# PORT.net
KiCad netlist of a schematic drawn in Altium Designer
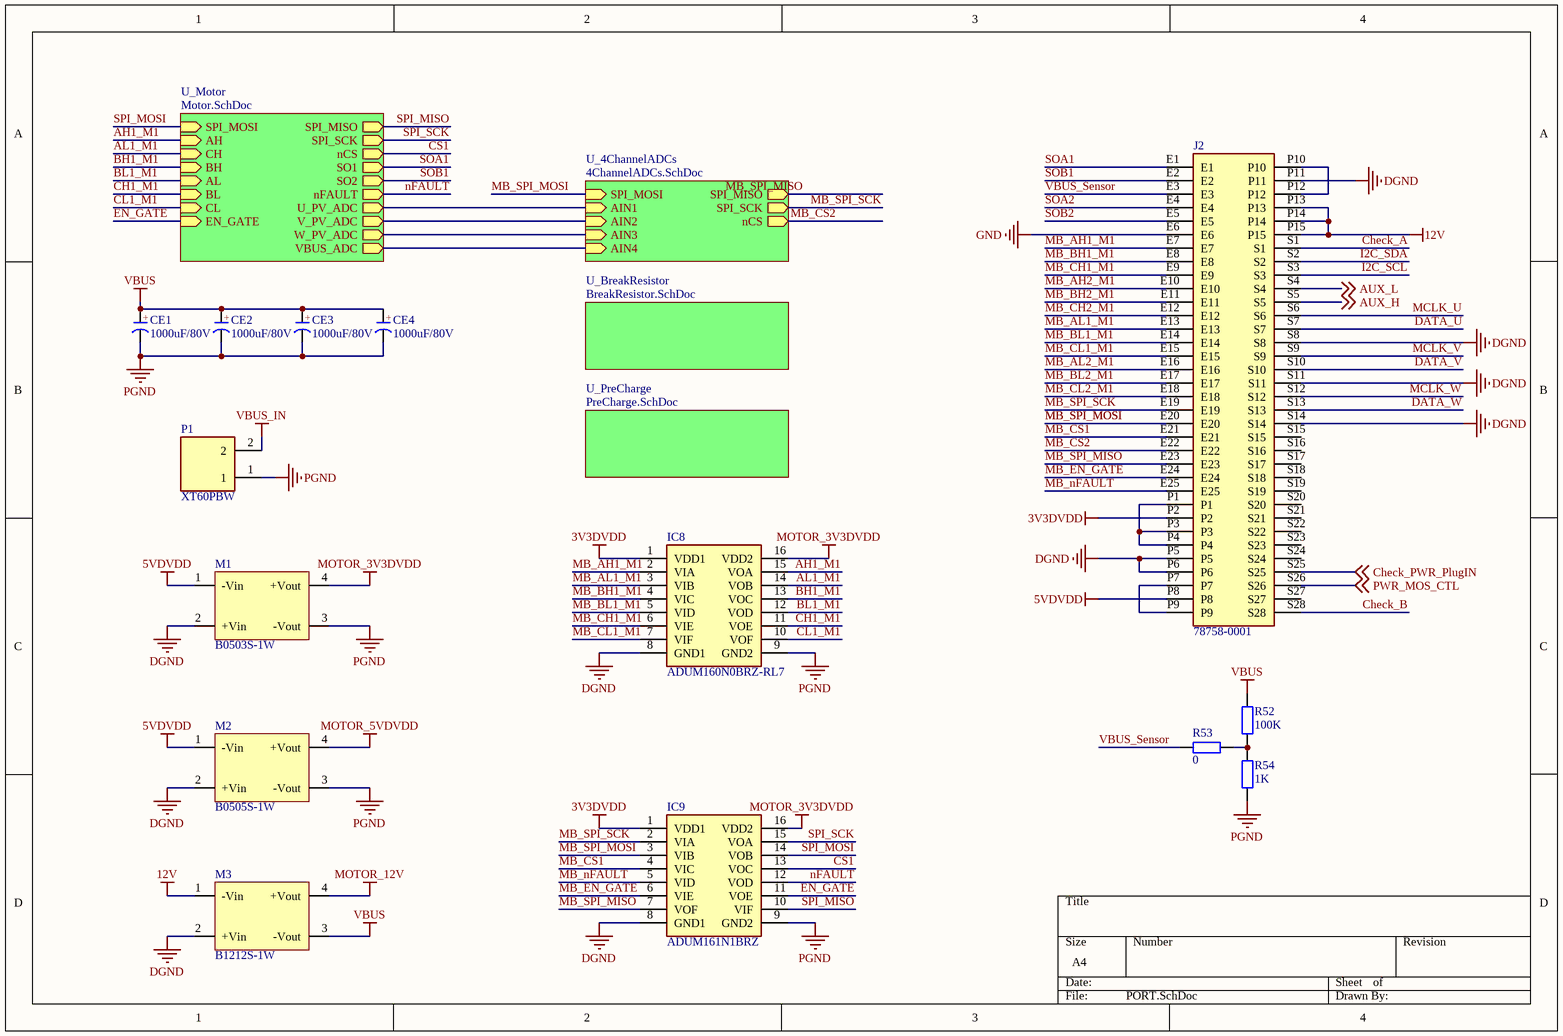
[diagram p0: PORT.SchDoc]

(export (version "E")
  (design (tool "Eeschema 10.0.6"))
  (components
    (comp (ref "CE1")
      (value "1000uF/80V")
      (footprint "CAP 7.5*18*35.5 - BK")
      (description "直插电解电容")
      (libsource (lib "0.1 - 电阻-电容-电感") (part "CE"))
    )
    (comp (ref "CE2")
      (value "1000uF/80V")
      (footprint "CAP 7.5*18*35.5 - BK")
      (description "直插电解电容")
      (libsource (lib "0.1 - 电阻-电容-电感") (part "CE"))
    )
    (comp (ref "CE3")
      (value "1000uF/80V")
      (footprint "CAP 7.5*18*35.5 - BK")
      (description "直插电解电容")
      (libsource (lib "0.1 - 电阻-电容-电感") (part "CE"))
    )
    (comp (ref "CE4")
      (value "1000uF/80V")
      (footprint "CAP 7.5*18*35.5 - BK")
      (description "直插电解电容")
      (libsource (lib "0.1 - 电阻-电容-电感") (part "CE"))
    )
    (comp (ref "IC8")
      (value "ADUM160N0BRZ-RL7")
      (footprint "SkylakeADPcbLib:SOIC127P600X175-16N")
      (description "Integrated Circuit")
      (fields (field (name "MOUSER PART NUMBER") "584-ADUM160N0BRZ-RL7"))
      (libsource (lib "*") (part "ADUM160N0BRZ-RL7"))
    )
    (comp (ref "IC9")
      (value "ADUM161N1BRZ")
      (footprint "SkylakeADPcbLib:SOIC127P600X175-16N")
      (description "Integrated Circuit")
      (fields (field (name "MOUSER PART NUMBER") "584-ADUM161N1BRZ"))
      (libsource (lib "*") (part "ADUM161N1BRZ"))
    )
    (comp (ref "J2")
      (value "78758-0001")
      (footprint "SkylakeADPcbLib:78758-0001")
      (description "Connector")
      (fields (field (name "MOUSER PART NUMBER") "538-78758-0001"))
      (libsource (lib "*") (part "78758-0001"))
    )
    (comp (ref "M1")
      (value "B0503S-1W")
      (footprint "B0505S-1W")
      (description "DC-DC模块")
      (fields (field (name "版权归属") "封装库来自淘宝 ID：黄晶宝石"))
      (libsource (lib "0.9 - 模块") (part "B0505S-1W"))
    )
    (comp (ref "M2")
      (value "B0505S-1W")
      (footprint "B0505S-1W")
      (description "DC-DC模块")
      (fields (field (name "版权归属") "封装库来自淘宝 ID：黄晶宝石"))
      (libsource (lib "0.9 - 模块") (part "B0505S-1W"))
    )
    (comp (ref "M3")
      (value "B1212S-1W")
      (footprint "B0505S-1W")
      (description "DC-DC模块")
      (fields (field (name "版权归属") "封装库来自淘宝 ID：黄晶宝石"))
      (libsource (lib "0.9 - 模块") (part "B0505S-1W"))
    )
    (comp (ref "P1")
      (value "XT60PBW")
      (footprint "XT60")
      (libsource (lib "SkylakeADSchLib") (part "XT60PBW"))
    )
    (comp (ref "R52")
      (value "100K")
      (footprint "R 0603_L")
      (description "贴片电阻")
      (libsource (lib "0.1 - 电阻-电容-电感") (part "R"))
    )
    (comp (ref "R53")
      (value "0")
      (footprint "R 0603_L")
      (description "贴片电阻")
      (libsource (lib "0.1 - 电阻-电容-电感") (part "R"))
    )
    (comp (ref "R54")
      (value "1K")
      (footprint "R 0603_L")
      (description "贴片电阻")
      (libsource (lib "0.1 - 电阻-电容-电感") (part "R"))
    )
  )
  (nets
    (net (code "1") (name "/AH1_M1") (class "Default")
      (node (ref "IC8") (pin "15") (pinfunction "VOA_15") (pintype "passive"))
    )
    (net (code "2") (name "/AL1_M1") (class "Default")
      (node (ref "IC8") (pin "14") (pinfunction "VOB_14") (pintype "passive"))
    )
    (net (code "3") (name "/BH1_M1") (class "Default")
      (node (ref "IC8") (pin "13") (pinfunction "VOC_13") (pintype "passive"))
    )
    (net (code "4") (name "/BL1_M1") (class "Default")
      (node (ref "IC8") (pin "12") (pinfunction "VOD_12") (pintype "passive"))
    )
    (net (code "5") (name "/CH1_M1") (class "Default")
      (node (ref "IC8") (pin "11") (pinfunction "VOE_11") (pintype "passive"))
    )
    (net (code "6") (name "/CL1_M1") (class "Default")
      (node (ref "IC8") (pin "10") (pinfunction "VOF_10") (pintype "passive"))
    )
    (net (code "7") (name "/CS1") (class "Default")
      (node (ref "IC9") (pin "13") (pinfunction "VOC_13") (pintype "passive"))
    )
    (net (code "8") (name "/Check_A") (class "Default")
      (node (ref "J2") (pin "S1") (pinfunction "S1_S1") (pintype "passive"))
    )
    (net (code "9") (name "/Check_B") (class "Default")
      (node (ref "J2") (pin "S28") (pinfunction "S28_S28") (pintype "passive"))
    )
    (net (code "10") (name "/DATA_U") (class "Default")
      (node (ref "J2") (pin "S7") (pinfunction "S7_S7") (pintype "passive"))
    )
    (net (code "11") (name "/DATA_V") (class "Default")
      (node (ref "J2") (pin "S10") (pinfunction "S10_S10") (pintype "passive"))
    )
    (net (code "12") (name "/DATA_W") (class "Default")
      (node (ref "J2") (pin "S13") (pinfunction "S13_S13") (pintype "passive"))
    )
    (net (code "13") (name "/EN_GATE") (class "Default")
      (node (ref "IC9") (pin "11") (pinfunction "VOE_11") (pintype "passive"))
    )
    (net (code "14") (name "/I2C_SCL") (class "Default")
      (node (ref "J2") (pin "S3") (pinfunction "S3_S3") (pintype "passive"))
    )
    (net (code "15") (name "/I2C_SDA") (class "Default")
      (node (ref "J2") (pin "S2") (pinfunction "S2_S2") (pintype "passive"))
    )
    (net (code "16") (name "/MB_AH1_M1") (class "Default")
      (node (ref "IC8") (pin "2") (pinfunction "VIA_2") (pintype "passive"))
      (node (ref "J2") (pin "E7") (pinfunction "E7_E7") (pintype "passive"))
    )
    (net (code "17") (name "/MB_AH2_M1") (class "Default")
      (node (ref "J2") (pin "E10") (pinfunction "E10_E10") (pintype "passive"))
    )
    (net (code "18") (name "/MB_AL1_M1") (class "Default")
      (node (ref "IC8") (pin "3") (pinfunction "VIB_3") (pintype "passive"))
      (node (ref "J2") (pin "E13") (pinfunction "E13_E13") (pintype "passive"))
    )
    (net (code "19") (name "/MB_AL2_M1") (class "Default")
      (node (ref "J2") (pin "E16") (pinfunction "E16_E16") (pintype "passive"))
    )
    (net (code "20") (name "/MB_BH1_M1") (class "Default")
      (node (ref "IC8") (pin "4") (pinfunction "VIC_4") (pintype "passive"))
      (node (ref "J2") (pin "E8") (pinfunction "E8_E8") (pintype "passive"))
    )
    (net (code "21") (name "/MB_BH2_M1") (class "Default")
      (node (ref "J2") (pin "E11") (pinfunction "E11_E11") (pintype "passive"))
    )
    (net (code "22") (name "/MB_BL1_M1") (class "Default")
      (node (ref "IC8") (pin "5") (pinfunction "VID_5") (pintype "passive"))
      (node (ref "J2") (pin "E14") (pinfunction "E14_E14") (pintype "passive"))
    )
    (net (code "23") (name "/MB_BL2_M1") (class "Default")
      (node (ref "J2") (pin "E17") (pinfunction "E17_E17") (pintype "passive"))
    )
    (net (code "24") (name "/MB_CH1_M1") (class "Default")
      (node (ref "IC8") (pin "6") (pinfunction "VIE_6") (pintype "passive"))
      (node (ref "J2") (pin "E9") (pinfunction "E9_E9") (pintype "passive"))
    )
    (net (code "25") (name "/MB_CH2_M1") (class "Default")
      (node (ref "J2") (pin "E12") (pinfunction "E12_E12") (pintype "passive"))
    )
    (net (code "26") (name "/MB_CL1_M1") (class "Default")
      (node (ref "IC8") (pin "7") (pinfunction "VIF_7") (pintype "passive"))
      (node (ref "J2") (pin "E15") (pinfunction "E15_E15") (pintype "passive"))
    )
    (net (code "27") (name "/MB_CL2_M1") (class "Default")
      (node (ref "J2") (pin "E18") (pinfunction "E18_E18") (pintype "passive"))
    )
    (net (code "28") (name "/MB_CS1") (class "Default")
      (node (ref "IC9") (pin "4") (pinfunction "VIC_4") (pintype "passive"))
      (node (ref "J2") (pin "E21") (pinfunction "E21_E21") (pintype "passive"))
    )
    (net (code "29") (name "/MB_CS2") (class "Default")
      (node (ref "J2") (pin "E22") (pinfunction "E22_E22") (pintype "passive"))
    )
    (net (code "30") (name "/MB_EN_GATE") (class "Default")
      (node (ref "IC9") (pin "6") (pinfunction "VIE_6") (pintype "passive"))
      (node (ref "J2") (pin "E24") (pinfunction "E24_E24") (pintype "passive"))
    )
    (net (code "31") (name "/MB_SPI_MISO") (class "Default")
      (node (ref "IC9") (pin "7") (pinfunction "VOF_7") (pintype "passive"))
      (node (ref "J2") (pin "E23") (pinfunction "E23_E23") (pintype "passive"))
    )
    (net (code "32") (name "/MB_SPI_MOSI") (class "Default")
      (node (ref "IC9") (pin "3") (pinfunction "VIB_3") (pintype "passive"))
      (node (ref "J2") (pin "E20") (pinfunction "E20_E20") (pintype "passive"))
    )
    (net (code "33") (name "/MB_SPI_SCK") (class "Default")
      (node (ref "IC9") (pin "2") (pinfunction "VIA_2") (pintype "passive"))
      (node (ref "J2") (pin "E19") (pinfunction "E19_E19") (pintype "passive"))
    )
    (net (code "34") (name "/MB_nFAULT") (class "Default")
      (node (ref "IC9") (pin "5") (pinfunction "VID_5") (pintype "passive"))
      (node (ref "J2") (pin "E25") (pinfunction "E25_E25") (pintype "passive"))
    )
    (net (code "35") (name "/MCLK_U") (class "Default")
      (node (ref "J2") (pin "S6") (pinfunction "S6_S6") (pintype "passive"))
    )
    (net (code "36") (name "/MCLK_V") (class "Default")
      (node (ref "J2") (pin "S9") (pinfunction "S9_S9") (pintype "passive"))
    )
    (net (code "37") (name "/MCLK_W") (class "Default")
      (node (ref "J2") (pin "S12") (pinfunction "S12_S12") (pintype "passive"))
    )
    (net (code "38") (name "/SOA1") (class "Default")
      (node (ref "J2") (pin "E1") (pinfunction "E1_E1") (pintype "passive"))
    )
    (net (code "39") (name "/SOA2") (class "Default")
      (node (ref "J2") (pin "E4") (pinfunction "E4_E4") (pintype "passive"))
    )
    (net (code "40") (name "/SOB1") (class "Default")
      (node (ref "J2") (pin "E2") (pinfunction "E2_E2") (pintype "passive"))
    )
    (net (code "41") (name "/SOB2") (class "Default")
      (node (ref "J2") (pin "E5") (pinfunction "E5_E5") (pintype "passive"))
    )
    (net (code "42") (name "/SPI_MISO") (class "Default")
      (node (ref "IC9") (pin "10") (pinfunction "VIF_10") (pintype "passive"))
    )
    (net (code "43") (name "/SPI_MOSI") (class "Default")
      (node (ref "IC9") (pin "14") (pinfunction "VOB_14") (pintype "passive"))
    )
    (net (code "44") (name "/SPI_SCK") (class "Default")
      (node (ref "IC9") (pin "15") (pinfunction "VOA_15") (pintype "passive"))
    )
    (net (code "47") (name "/VBUS_Sensor") (class "Default")
      (node (ref "J2") (pin "E3") (pinfunction "E3_E3") (pintype "passive"))
      (node (ref "R53") (pin "2") (pinfunction "2_2") (pintype "passive"))
    )
    (net (code "50") (name "/nFAULT") (class "Default")
      (node (ref "IC9") (pin "12") (pinfunction "VOD_12") (pintype "passive"))
    )
    (net (code "51") (name "3V3DVDD") (class "Default")
      (node (ref "IC8") (pin "1") (pinfunction "VDD1_1") (pintype "passive"))
      (node (ref "IC9") (pin "1") (pinfunction "VDD1_1") (pintype "passive"))
      (node (ref "J2") (pin "P2") (pinfunction "P2_P2") (pintype "passive"))
    )
    (net (code "52") (name "5VDVDD") (class "Default")
      (node (ref "J2") (pin "P8") (pinfunction "P8_P8") (pintype "passive"))
      (node (ref "M1") (pin "1") (pinfunction "-Vin_1") (pintype "passive"))
      (node (ref "M2") (pin "1") (pinfunction "-Vin_1") (pintype "passive"))
    )
    (net (code "53") (name "12V") (class "Default")
      (node (ref "J2") (pin "P13") (pinfunction "P13_P13") (pintype "passive"))
      (node (ref "J2") (pin "P14") (pinfunction "P14_P14") (pintype "passive"))
      (node (ref "J2") (pin "P15") (pinfunction "P15_P15") (pintype "passive"))
      (node (ref "M3") (pin "1") (pinfunction "-Vin_1") (pintype "passive"))
    )
    (net (code "54") (name "AUX_H") (class "Default")
      (node (ref "J2") (pin "S5") (pinfunction "S5_S5") (pintype "passive"))
    )
    (net (code "55") (name "AUX_L") (class "Default")
      (node (ref "J2") (pin "S4") (pinfunction "S4_S4") (pintype "passive"))
    )
    (net (code "56") (name "Check_PWR_PlugIN") (class "Default")
      (node (ref "J2") (pin "S25") (pinfunction "S25_S25") (pintype "passive"))
    )
    (net (code "57") (name "DGND") (class "Default")
      (node (ref "IC8") (pin "8") (pinfunction "GND1_8") (pintype "passive"))
      (node (ref "IC9") (pin "8") (pinfunction "GND1_8") (pintype "passive"))
      (node (ref "J2") (pin "P11") (pinfunction "P11_P11") (pintype "passive"))
      (node (ref "J2") (pin "P5") (pinfunction "P5_P5") (pintype "passive"))
      (node (ref "J2") (pin "P6") (pinfunction "P6_P6") (pintype "passive"))
      (node (ref "J2") (pin "S11") (pinfunction "S11_S11") (pintype "passive"))
      (node (ref "J2") (pin "S14") (pinfunction "S14_S14") (pintype "passive"))
      (node (ref "J2") (pin "S8") (pinfunction "S8_S8") (pintype "passive"))
      (node (ref "M1") (pin "2") (pinfunction "+Vin_2") (pintype "passive"))
      (node (ref "M2") (pin "2") (pinfunction "+Vin_2") (pintype "passive"))
      (node (ref "M3") (pin "2") (pinfunction "+Vin_2") (pintype "passive"))
    )
    (net (code "58") (name "GND") (class "Default")
      (node (ref "J2") (pin "E6") (pinfunction "E6_E6") (pintype "passive"))
    )
    (net (code "59") (name "MOTOR_3V3DVDD") (class "Default")
      (node (ref "IC8") (pin "16") (pinfunction "VDD2_16") (pintype "passive"))
      (node (ref "IC9") (pin "16") (pinfunction "VDD2_16") (pintype "passive"))
      (node (ref "M1") (pin "4") (pinfunction "+Vout_4") (pintype "passive"))
    )
    (net (code "60") (name "MOTOR_5VDVDD") (class "Default")
      (node (ref "M2") (pin "4") (pinfunction "+Vout_4") (pintype "passive"))
    )
    (net (code "61") (name "MOTOR_12V") (class "Default")
      (node (ref "M3") (pin "4") (pinfunction "+Vout_4") (pintype "passive"))
    )
    (net (code "62") (name "Net-(J2-PadP1)") (class "Default")
      (node (ref "J2") (pin "P1") (pinfunction "P1_P1") (pintype "passive"))
      (node (ref "J2") (pin "P3") (pinfunction "P3_P3") (pintype "passive"))
      (node (ref "J2") (pin "P4") (pinfunction "P4_P4") (pintype "passive"))
    )
    (net (code "63") (name "Net-(J2-PadP7)") (class "Default")
      (node (ref "J2") (pin "P7") (pinfunction "P7_P7") (pintype "passive"))
      (node (ref "J2") (pin "P9") (pinfunction "P9_P9") (pintype "passive"))
    )
    (net (code "64") (name "Net-(J2-PadP10)") (class "Default")
      (node (ref "J2") (pin "P10") (pinfunction "P10_P10") (pintype "passive"))
      (node (ref "J2") (pin "P12") (pinfunction "P12_P12") (pintype "passive"))
    )
    (net (code "65") (name "Net-(R52-Pad1)") (class "Default")
      (node (ref "R52") (pin "1") (pinfunction "1_1") (pintype "passive"))
      (node (ref "R53") (pin "1") (pinfunction "1_1") (pintype "passive"))
      (node (ref "R54") (pin "2") (pinfunction "2_2") (pintype "passive"))
    )
    (net (code "66") (name "PGND") (class "Default")
      (node (ref "CE1") (pin "2") (pinfunction "K_2") (pintype "passive"))
      (node (ref "CE2") (pin "2") (pinfunction "K_2") (pintype "passive"))
      (node (ref "CE3") (pin "2") (pinfunction "K_2") (pintype "passive"))
      (node (ref "CE4") (pin "2") (pinfunction "K_2") (pintype "passive"))
      (node (ref "IC8") (pin "9") (pinfunction "GND2_9") (pintype "passive"))
      (node (ref "IC9") (pin "9") (pinfunction "GND2_9") (pintype "passive"))
      (node (ref "M1") (pin "3") (pinfunction "-Vout_3") (pintype "passive"))
      (node (ref "M2") (pin "3") (pinfunction "-Vout_3") (pintype "passive"))
      (node (ref "P1") (pin "1") (pinfunction "1_1") (pintype "passive"))
      (node (ref "R54") (pin "1") (pinfunction "1_1") (pintype "passive"))
    )
    (net (code "67") (name "PWR_MOS_CTL") (class "Default")
      (node (ref "J2") (pin "S26") (pinfunction "S26_S26") (pintype "passive"))
    )
    (net (code "68") (name "VBUS") (class "Default")
      (node (ref "CE1") (pin "1") (pinfunction "A_1") (pintype "passive"))
      (node (ref "CE2") (pin "1") (pinfunction "A_1") (pintype "passive"))
      (node (ref "CE3") (pin "1") (pinfunction "A_1") (pintype "passive"))
      (node (ref "CE4") (pin "1") (pinfunction "A_1") (pintype "passive"))
      (node (ref "M3") (pin "3") (pinfunction "-Vout_3") (pintype "passive"))
      (node (ref "R52") (pin "2") (pinfunction "2_2") (pintype "passive"))
    )
    (net (code "69") (name "VBUS_IN") (class "Default")
      (node (ref "P1") (pin "2") (pinfunction "2_2") (pintype "passive"))
    )
    (net (code "70") (name "unconnected-(J2-PadS15)") (class "Default")
      (node (ref "J2") (pin "S15") (pinfunction "S15_S15") (pintype "passive"))
    )
    (net (code "71") (name "unconnected-(J2-PadS16)") (class "Default")
      (node (ref "J2") (pin "S16") (pinfunction "S16_S16") (pintype "passive"))
    )
    (net (code "72") (name "unconnected-(J2-PadS17)") (class "Default")
      (node (ref "J2") (pin "S17") (pinfunction "S17_S17") (pintype "passive"))
    )
    (net (code "73") (name "unconnected-(J2-PadS18)") (class "Default")
      (node (ref "J2") (pin "S18") (pinfunction "S18_S18") (pintype "passive"))
    )
    (net (code "74") (name "unconnected-(J2-PadS19)") (class "Default")
      (node (ref "J2") (pin "S19") (pinfunction "S19_S19") (pintype "passive"))
    )
    (net (code "75") (name "unconnected-(J2-PadS20)") (class "Default")
      (node (ref "J2") (pin "S20") (pinfunction "S20_S20") (pintype "passive"))
    )
    (net (code "76") (name "unconnected-(J2-PadS21)") (class "Default")
      (node (ref "J2") (pin "S21") (pinfunction "S21_S21") (pintype "passive"))
    )
    (net (code "77") (name "unconnected-(J2-PadS22)") (class "Default")
      (node (ref "J2") (pin "S22") (pinfunction "S22_S22") (pintype "passive"))
    )
    (net (code "78") (name "unconnected-(J2-PadS23)") (class "Default")
      (node (ref "J2") (pin "S23") (pinfunction "S23_S23") (pintype "passive"))
    )
    (net (code "79") (name "unconnected-(J2-PadS24)") (class "Default")
      (node (ref "J2") (pin "S24") (pinfunction "S24_S24") (pintype "passive"))
    )
    (net (code "80") (name "unconnected-(J2-PadS27)") (class "Default")
      (node (ref "J2") (pin "S27") (pinfunction "S27_S27") (pintype "passive"))
    )
  )
)
